# 2_0.net
KiCad netlist of a schematic drawn in Altium Designer
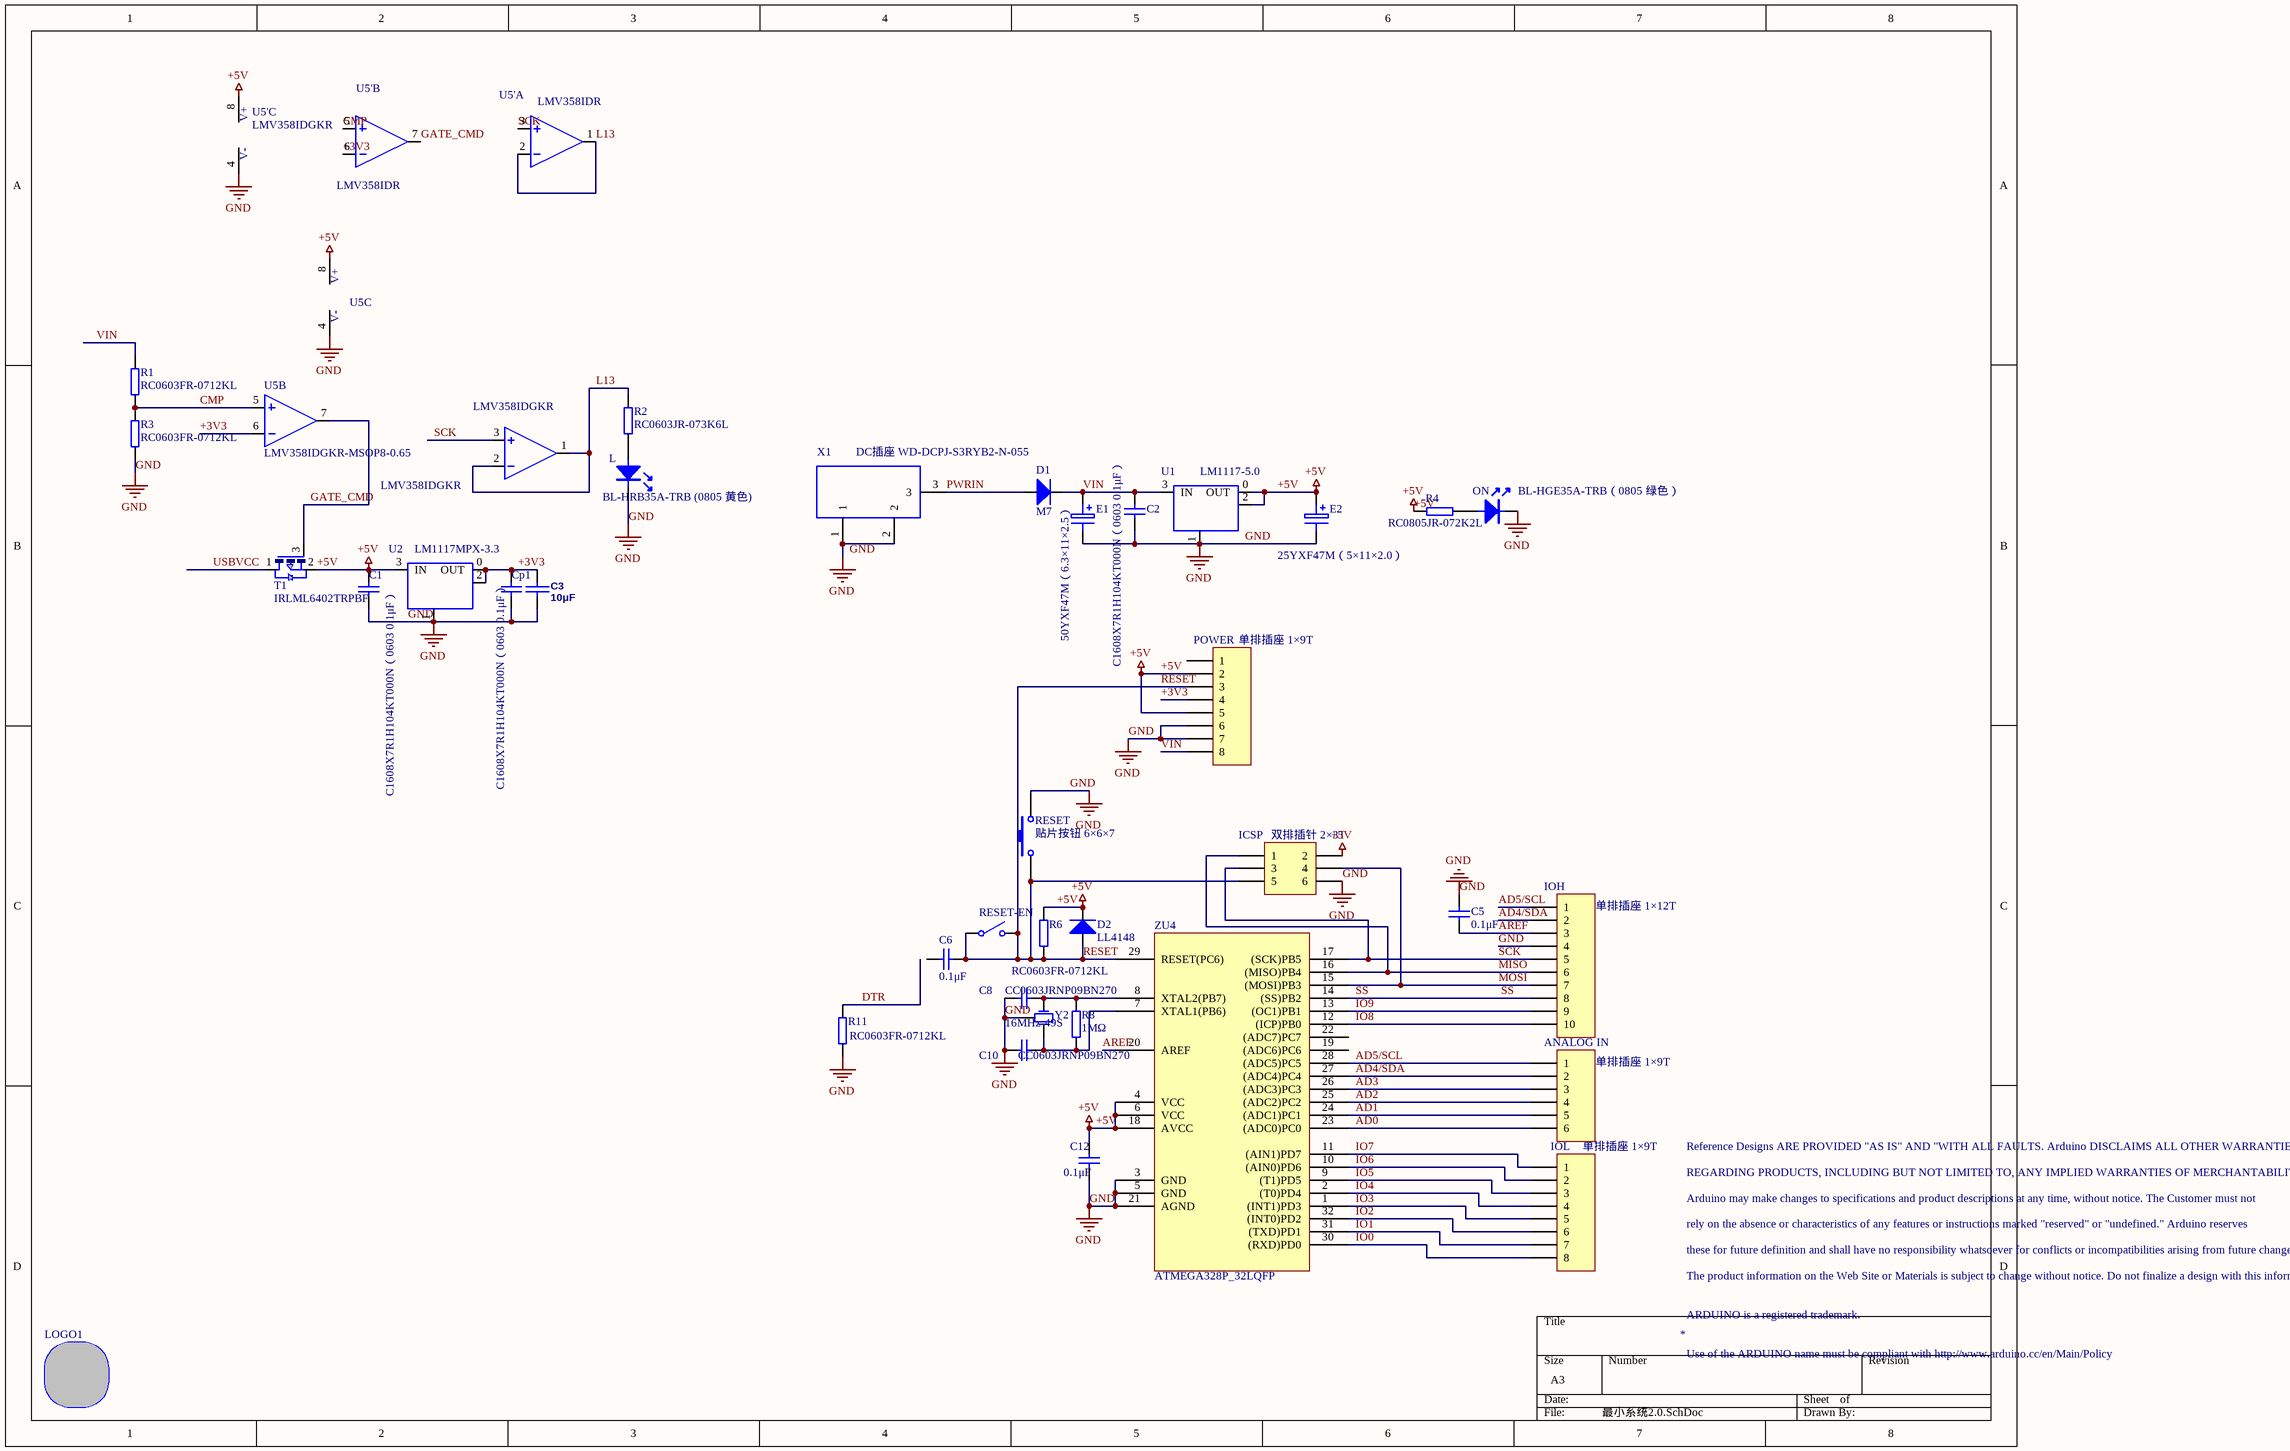
[diagram p0: 最小系统2.0.SchDoc]

(export (version "E")
  (design (tool "Eeschema 10.0.6"))
  (components
    (comp (ref "ANALOG IN")
      (value "单排插座 1×9T")
      (footprint "HDR1X6Z")
      (description "Header, 6-Pin")
      (fields (field (name "PUBLISHER") "Altium Limited"))
      (libsource (lib "Miscellaneous Connectors") (part "Header 6"))
    )
    (comp (ref "C1")
      (value "C1608X7R1H104KT000N（0603 0.1μF）")
      (footprint "0603C")
      (description "Capacitor")
      (fields (field (name "PUBLISHER") "Altium Limited"))
      (libsource (lib "*") (part "Cap"))
    )
    (comp (ref "C2")
      (value "C1608X7R1H104KT000N（0603 0.1μF）")
      (footprint "0603C")
      (description "Capacitor")
      (fields (field (name "PUBLISHER") "Altium Limited"))
      (libsource (lib "Miscellaneous Devices") (part "Cap"))
    )
    (comp (ref "C3")
      (value "10μF")
      (footprint "1206C")
      (description "Capacitor")
      (libsource (lib "*") (part "CAP"))
    )
    (comp (ref "C5")
      (value "0.1μF")
      (footprint "0603C")
      (description "Capacitor")
      (fields (field (name "PUBLISHER") "Altium Limited"))
      (libsource (lib "Miscellaneous Devices") (part "Cap"))
    )
    (comp (ref "C6")
      (value "0.1μF")
      (footprint "0603C")
      (description "Capacitor")
      (fields (field (name "PUBLISHER") "Altium Limited"))
      (libsource (lib "Miscellaneous Devices") (part "Cap"))
    )
    (comp (ref "C8")
      (value "CC0603JRNP09BN270")
      (footprint "0603C")
      (description "Capacitor")
      (fields (field (name "PUBLISHER") "Altium Limited"))
      (libsource (lib "Miscellaneous Devices") (part "Cap"))
    )
    (comp (ref "C10")
      (value "CC0603JRNP09BN270")
      (footprint "0603C")
      (description "Capacitor")
      (fields (field (name "PUBLISHER") "Altium Limited"))
      (libsource (lib "Miscellaneous Devices") (part "Cap"))
    )
    (comp (ref "C12")
      (value "0.1μF")
      (footprint "0603C")
      (description "Capacitor")
      (fields (field (name "PUBLISHER") "Altium Limited"))
      (libsource (lib "Miscellaneous Devices") (part "Cap"))
    )
    (comp (ref "Cp1")
      (value "C1608X7R1H104KT000N（0603 0.1μF）")
      (footprint "0603C")
      (description "Capacitor")
      (fields (field (name "PUBLISHER") "Altium Limited"))
      (libsource (lib "*") (part "Cap"))
    )
    (comp (ref "D1")
      (value "M7")
      (footprint "M7")
      (description "D")
      (libsource (lib "Miscellaneous Devices") (part "M7"))
    )
    (comp (ref "D2")
      (value "LL4148")
      (footprint "D1206")
      (description "D")
      (libsource (lib "Miscellaneous Devices") (part "M7"))
    )
    (comp (ref "E1")
      (value "50YXF47M（6.3×11×2.5）")
      (footprint "RB 6.3×11×2.5")
      (libsource (lib "Miscellaneous Devices") (part "E"))
    )
    (comp (ref "E2")
      (value "25YXF47M（5×11×2.0）")
      (footprint "RB 6.3×11×2.5")
      (libsource (lib "Miscellaneous Devices") (part "E"))
    )
    (comp (ref "ICSP")
      (value "双排插针 2×3T")
      (footprint "HDR2X3")
      (description "Header, 3-Pin, Dual row")
      (fields (field (name "PUBLISHER") "Altium Limited"))
      (libsource (lib "Miscellaneous Connectors") (part "Header 3X2"))
    )
    (comp (ref "IOH")
      (value "单排插座 1×12T")
      (footprint "HDR1X10Z")
      (description "Header, 10-Pin")
      (fields (field (name "PUBLISHER") "Altium Limited"))
      (libsource (lib "Miscellaneous Connectors") (part "Header 10"))
    )
    (comp (ref "IOL")
      (value "单排插座 1×9T")
      (footprint "HDR1X8Z")
      (description "Header, 8-Pin")
      (fields (field (name "PUBLISHER") "Altium Limited"))
      (libsource (lib "Miscellaneous Connectors") (part "Header 8"))
    )
    (comp (ref "L")
      (value "BL-HRB35A-TRB (0805 黄色)")
      (footprint "LED0805-Y")
      (libsource (lib "Miscellaneous Devices") (part "LED"))
    )
    (comp (ref "LOGO1")
      (value "LOGO")
      (footprint "USB_LOGO")
      (libsource (lib "Miscellaneous Connectors") (part "LOGO"))
    )
    (comp (ref "ON")
      (value "BL-HGE35A-TRB（0805 绿色）")
      (footprint "LED0805-R")
      (libsource (lib "Miscellaneous Devices") (part "LED"))
    )
    (comp (ref "POWER")
      (value "单排插座 1×9T")
      (footprint "HDR1X8Z")
      (description "Header, 8-Pin")
      (fields (field (name "PUBLISHER") "Altium Limited"))
      (libsource (lib "Miscellaneous Connectors") (part "Header 8"))
    )
    (comp (ref "R1")
      (value "RC0603FR-0712KL")
      (footprint "0603R")
      (description "Resistor")
      (libsource (lib "Miscellaneous Devices") (part "R"))
    )
    (comp (ref "R2")
      (value "RC0603JR-073K6L")
      (footprint "0603R")
      (description "Resistor")
      (libsource (lib "Miscellaneous Devices") (part "R"))
    )
    (comp (ref "R3")
      (value "RC0603FR-0712KL")
      (footprint "0603R")
      (description "Resistor")
      (libsource (lib "Miscellaneous Devices") (part "R"))
    )
    (comp (ref "R4")
      (value "RC0805JR-072K2L")
      (footprint "0805/R")
      (description "Resistor")
      (libsource (lib "Miscellaneous Devices") (part "R"))
    )
    (comp (ref "R6")
      (value "RC0603FR-0712KL")
      (footprint "0603R")
      (description "Resistor")
      (libsource (lib "Miscellaneous Devices") (part "R"))
    )
    (comp (ref "R8")
      (value "1MΩ")
      (footprint "0603R")
      (description "Resistor")
      (libsource (lib "Miscellaneous Devices") (part "R"))
    )
    (comp (ref "R11")
      (value "RC0603FR-0712KL")
      (footprint "0603R")
      (description "Resistor")
      (libsource (lib "Miscellaneous Devices") (part "R"))
    )
    (comp (ref "RESET")
      (value "贴片按钮 6×6×7")
      (footprint "按钮/SO")
      (description "Switch")
      (fields (field (name "PUBLISHER") "Altium Limited"))
      (libsource (lib "Miscellaneous Devices") (part "SW-PB"))
    )
    (comp (ref "RESET-EN")
      (value "~")
      (footprint "0101")
      (description "Single-Pole, Single-Throw Switch")
      (fields (field (name "PUBLISHER") "Altium Limited"))
      (libsource (lib "Miscellaneous Devices") (part "SW-SPST"))
    )
    (comp (ref "T1")
      (value "IRLML6402TRPBF")
      (footprint "MOSFET")
      (libsource (lib "Miscellaneous Devices") (part "PMOSSOT23"))
    )
    (comp (ref "U$1") (value "*") (footprint "MARK") (libsource (lib "SmartPrj") (part "DISCLAIMER")))
    (comp (ref "U1")
      (value "LM1117-5.0")
      (footprint "SOT223")
      (libsource (lib "Miscellaneous Devices") (part "LM1117"))
    )
    (comp (ref "U2")
      (value "LM1117MPX-3.3")
      (footprint "SOT223")
      (libsource (lib "Miscellaneous Devices") (part "LM1117"))
    )
    (comp (ref "U5")
      (value "LMV358IDGKR")
      (footprint "MSOP8-0.65")
      (libsource (lib "Miscellaneous Devices") (part "LMV358MMX"))
    )
    (comp (ref "U5'")
      (value "LMV358IDR")
      (footprint "so-8")
      (libsource (lib "Miscellaneous Devices") (part "LMV358MMX"))
    )
    (comp (ref "X1")
      (value "DC插座 WD-DCPJ-S3RYB2-N-055")
      (footprint "DC_IN")
      (description "POWERSUPPLY_DC21MMX")
      (libsource (lib "Miscellaneous Connectors") (part "DC_IN"))
    )
    (comp (ref "Y2")
      (value "16MHz-49S")
      (footprint "XTAL-49S")
      (description "3pXTAL")
      (libsource (lib "Miscellaneous Devices") (part "XTAL1"))
    )
    (comp (ref "ZU4")
      (value "ATMEGA328P_32LQFP")
      (footprint "LQFP32")
      (description "Arduino ATMEGA328P")
      (libsource (lib "Miscellaneous Devices") (part "ATMEGA328P_32LQFP"))
    )
  )
  (nets
    (net (code "1") (name "+5V") (class "Default")
      (node (ref "C1") (pin "1") (pinfunction "1_1") (pintype "passive"))
      (node (ref "C12") (pin "2") (pinfunction "2_2") (pintype "passive"))
      (node (ref "D2") (pin "K") (pinfunction "K_K") (pintype "passive"))
      (node (ref "E2") (pin "1") (pintype "passive"))
      (node (ref "ICSP") (pin "2") (pinfunction "2_2") (pintype "passive"))
      (node (ref "POWER") (pin "2") (pinfunction "2_2") (pintype "passive"))
      (node (ref "POWER") (pin "5") (pinfunction "5_5") (pintype "passive"))
      (node (ref "R4") (pin "2") (pintype "passive"))
      (node (ref "R6") (pin "1") (pintype "passive"))
      (node (ref "T1") (pin "2") (pinfunction "S_2") (pintype "passive"))
      (node (ref "U1") (pin "0") (pinfunction "OUT_0") (pintype "passive"))
      (node (ref "U1") (pin "2") (pinfunction "OUT@1_2") (pintype "passive"))
      (node (ref "U2") (pin "3") (pinfunction "IN_3") (pintype "passive"))
      (node (ref "U5") (pin "8") (pinfunction "V+_8") (pintype "passive"))
      (node (ref "U5'") (pin "8") (pinfunction "V+_8") (pintype "passive"))
      (node (ref "ZU4") (pin "18") (pinfunction "AVCC_18") (pintype "passive"))
      (node (ref "ZU4") (pin "4") (pinfunction "VCC_4") (pintype "passive"))
      (node (ref "ZU4") (pin "6") (pinfunction "VCC_6") (pintype "passive"))
    )
    (net (code "2") (name "/+3V3") (class "Default")
      (node (ref "C3") (pin "2") (pinfunction "2_2") (pintype "passive"))
      (node (ref "Cp1") (pin "1") (pinfunction "1_1") (pintype "passive"))
      (node (ref "POWER") (pin "4") (pinfunction "4_4") (pintype "passive"))
      (node (ref "U2") (pin "0") (pinfunction "OUT_0") (pintype "passive"))
      (node (ref "U2") (pin "2") (pinfunction "OUT@1_2") (pintype "passive"))
      (node (ref "U5") (pin "6") (pinfunction "-IN_6") (pintype "passive"))
      (node (ref "U5'") (pin "6") (pinfunction "-IN_6") (pintype "passive"))
    )
    (net (code "3") (name "/AD0") (class "Default")
      (node (ref "ANALOG IN") (pin "6") (pinfunction "6_6") (pintype "passive"))
      (node (ref "ZU4") (pin "23") (pinfunction "(ADC0)PC0_23") (pintype "passive"))
    )
    (net (code "4") (name "/AD1") (class "Default")
      (node (ref "ANALOG IN") (pin "5") (pinfunction "5_5") (pintype "passive"))
      (node (ref "ZU4") (pin "24") (pinfunction "(ADC1)PC1_24") (pintype "passive"))
    )
    (net (code "5") (name "/AD2") (class "Default")
      (node (ref "ANALOG IN") (pin "4") (pinfunction "4_4") (pintype "passive"))
      (node (ref "ZU4") (pin "25") (pinfunction "(ADC2)PC2_25") (pintype "passive"))
    )
    (net (code "6") (name "/AD3") (class "Default")
      (node (ref "ANALOG IN") (pin "3") (pinfunction "3_3") (pintype "passive"))
      (node (ref "ZU4") (pin "26") (pinfunction "(ADC3)PC3_26") (pintype "passive"))
    )
    (net (code "7") (name "/AD4{slash}SDA") (class "Default")
      (node (ref "ANALOG IN") (pin "2") (pinfunction "2_2") (pintype "passive"))
      (node (ref "IOH") (pin "2") (pinfunction "2_2") (pintype "passive"))
      (node (ref "ZU4") (pin "27") (pinfunction "(ADC4)PC4_27") (pintype "passive"))
    )
    (net (code "8") (name "/AD5{slash}SCL") (class "Default")
      (node (ref "ANALOG IN") (pin "1") (pinfunction "1_1") (pintype "passive"))
      (node (ref "IOH") (pin "1") (pinfunction "1_1") (pintype "passive"))
      (node (ref "ZU4") (pin "28") (pinfunction "(ADC5)PC5_28") (pintype "passive"))
    )
    (net (code "9") (name "/AREF") (class "Default")
      (node (ref "C5") (pin "1") (pinfunction "1_1") (pintype "passive"))
      (node (ref "IOH") (pin "3") (pinfunction "3_3") (pintype "passive"))
      (node (ref "ZU4") (pin "20") (pinfunction "AREF_20") (pintype "passive"))
    )
    (net (code "10") (name "/CMP") (class "Default")
      (node (ref "R1") (pin "2") (pintype "passive"))
      (node (ref "R3") (pin "1") (pintype "passive"))
      (node (ref "U5") (pin "5") (pinfunction "+IN_5") (pintype "passive"))
      (node (ref "U5'") (pin "5") (pinfunction "+IN_5") (pintype "passive"))
    )
    (net (code "11") (name "/DTR") (class "Default") (node (ref "R11") (pin "1") (pintype "passive")))
    (net (code "12") (name "/GATE_CMD") (class "Default")
      (node (ref "T1") (pin "3") (pinfunction "G_3") (pintype "passive"))
      (node (ref "U5") (pin "7") (pinfunction "OUT_7") (pintype "passive"))
      (node (ref "U5'") (pin "7") (pinfunction "OUT_7") (pintype "passive"))
    )
    (net (code "13") (name "/IO0") (class "Default")
      (node (ref "IOL") (pin "8") (pinfunction "8_8") (pintype "passive"))
      (node (ref "ZU4") (pin "30") (pinfunction "(RXD)PD0_30") (pintype "passive"))
    )
    (net (code "14") (name "/IO1") (class "Default")
      (node (ref "IOL") (pin "7") (pinfunction "7_7") (pintype "passive"))
      (node (ref "ZU4") (pin "31") (pinfunction "(TXD)PD1_31") (pintype "passive"))
    )
    (net (code "15") (name "/IO2") (class "Default")
      (node (ref "IOL") (pin "6") (pinfunction "6_6") (pintype "passive"))
      (node (ref "ZU4") (pin "32") (pinfunction "(INT0)PD2_32") (pintype "passive"))
    )
    (net (code "16") (name "/IO3") (class "Default")
      (node (ref "IOL") (pin "5") (pinfunction "5_5") (pintype "passive"))
      (node (ref "ZU4") (pin "1") (pinfunction "(INT1)PD3_1") (pintype "passive"))
    )
    (net (code "17") (name "/IO4") (class "Default")
      (node (ref "IOL") (pin "4") (pinfunction "4_4") (pintype "passive"))
      (node (ref "ZU4") (pin "2") (pinfunction "(T0)PD4_2") (pintype "passive"))
    )
    (net (code "18") (name "/IO5") (class "Default")
      (node (ref "IOL") (pin "3") (pinfunction "3_3") (pintype "passive"))
      (node (ref "ZU4") (pin "9") (pinfunction "(T1)PD5_9") (pintype "passive"))
    )
    (net (code "19") (name "/IO6") (class "Default")
      (node (ref "IOL") (pin "2") (pinfunction "2_2") (pintype "passive"))
      (node (ref "ZU4") (pin "10") (pinfunction "(AIN0)PD6_10") (pintype "passive"))
    )
    (net (code "20") (name "/IO7") (class "Default")
      (node (ref "IOL") (pin "1") (pinfunction "1_1") (pintype "passive"))
      (node (ref "ZU4") (pin "11") (pinfunction "(AIN1)PD7_11") (pintype "passive"))
    )
    (net (code "21") (name "/IO8") (class "Default")
      (node (ref "IOH") (pin "10") (pinfunction "10_10") (pintype "passive"))
      (node (ref "ZU4") (pin "12") (pinfunction "(ICP)PB0_12") (pintype "passive"))
    )
    (net (code "22") (name "/IO9") (class "Default")
      (node (ref "IOH") (pin "9") (pinfunction "9_9") (pintype "passive"))
      (node (ref "ZU4") (pin "13") (pinfunction "(OC1)PB1_13") (pintype "passive"))
    )
    (net (code "23") (name "/L13") (class "Default")
      (node (ref "R2") (pin "1") (pintype "passive"))
      (node (ref "U5") (pin "1") (pinfunction "OUT_1") (pintype "passive"))
      (node (ref "U5") (pin "2") (pinfunction "-IN_2") (pintype "passive"))
      (node (ref "U5'") (pin "1") (pinfunction "OUT_1") (pintype "passive"))
      (node (ref "U5'") (pin "2") (pinfunction "-IN_2") (pintype "passive"))
    )
    (net (code "24") (name "/MISO") (class "Default")
      (node (ref "ICSP") (pin "1") (pinfunction "1_1") (pintype "passive"))
      (node (ref "IOH") (pin "6") (pinfunction "6_6") (pintype "passive"))
      (node (ref "ZU4") (pin "16") (pinfunction "(MISO)PB4_16") (pintype "passive"))
    )
    (net (code "25") (name "/MOSI") (class "Default")
      (node (ref "ICSP") (pin "4") (pinfunction "4_4") (pintype "passive"))
      (node (ref "IOH") (pin "7") (pinfunction "7_7") (pintype "passive"))
      (node (ref "ZU4") (pin "15") (pinfunction "(MOSI)PB3_15") (pintype "passive"))
    )
    (net (code "26") (name "/PWRIN") (class "Default")
      (node (ref "D1") (pin "A") (pinfunction "A_A") (pintype "passive"))
      (node (ref "X1") (pin "3") (pinfunction "3_3") (pintype "passive"))
    )
    (net (code "27") (name "/RESET") (class "Default")
      (node (ref "C6") (pin "2") (pinfunction "2_2") (pintype "passive"))
      (node (ref "D2") (pin "A") (pinfunction "A_A") (pintype "passive"))
      (node (ref "ICSP") (pin "5") (pinfunction "5_5") (pintype "passive"))
      (node (ref "POWER") (pin "3") (pinfunction "3_3") (pintype "passive"))
      (node (ref "R6") (pin "2") (pintype "passive"))
      (node (ref "RESET") (pin "1") (pinfunction "1_1") (pintype "passive"))
      (node (ref "RESET-EN") (pin "1") (pinfunction "COMMON_1") (pintype "passive"))
      (node (ref "RESET-EN") (pin "2") (pinfunction "NO_2") (pintype "passive"))
      (node (ref "ZU4") (pin "29") (pinfunction "RESET(PC6)_29") (pintype "passive"))
    )
    (net (code "28") (name "/SCK") (class "Default")
      (node (ref "ICSP") (pin "3") (pinfunction "3_3") (pintype "passive"))
      (node (ref "IOH") (pin "5") (pinfunction "5_5") (pintype "passive"))
      (node (ref "U5") (pin "3") (pinfunction "+IN_3") (pintype "passive"))
      (node (ref "U5'") (pin "3") (pinfunction "+IN_3") (pintype "passive"))
      (node (ref "ZU4") (pin "17") (pinfunction "(SCK)PB5_17") (pintype "passive"))
    )
    (net (code "29") (name "/SS") (class "Default")
      (node (ref "IOH") (pin "8") (pinfunction "8_8") (pintype "passive"))
      (node (ref "ZU4") (pin "14") (pinfunction "(SS)PB2_14") (pintype "passive"))
    )
    (net (code "30") (name "/USBVCC") (class "Default")
      (node (ref "T1") (pin "1") (pinfunction "D_1") (pintype "passive"))
    )
    (net (code "31") (name "/VIN") (class "Default")
      (node (ref "C2") (pin "2") (pinfunction "2_2") (pintype "passive"))
      (node (ref "D1") (pin "K") (pinfunction "K_K") (pintype "passive"))
      (node (ref "E1") (pin "1") (pintype "passive"))
      (node (ref "POWER") (pin "8") (pinfunction "8_8") (pintype "passive"))
      (node (ref "R1") (pin "1") (pintype "passive"))
      (node (ref "U1") (pin "3") (pinfunction "IN_3") (pintype "passive"))
    )
    (net (code "32") (name "GND") (class "Default")
      (node (ref "C1") (pin "2") (pinfunction "2_2") (pintype "passive"))
      (node (ref "C10") (pin "1") (pinfunction "1_1") (pintype "passive"))
      (node (ref "C12") (pin "1") (pinfunction "1_1") (pintype "passive"))
      (node (ref "C2") (pin "1") (pinfunction "1_1") (pintype "passive"))
      (node (ref "C3") (pin "1") (pinfunction "1_1") (pintype "passive"))
      (node (ref "C5") (pin "2") (pinfunction "2_2") (pintype "passive"))
      (node (ref "C8") (pin "1") (pinfunction "1_1") (pintype "passive"))
      (node (ref "Cp1") (pin "2") (pinfunction "2_2") (pintype "passive"))
      (node (ref "E1") (pin "2") (pintype "passive"))
      (node (ref "E2") (pin "2") (pintype "passive"))
      (node (ref "ICSP") (pin "6") (pinfunction "6_6") (pintype "passive"))
      (node (ref "IOH") (pin "4") (pinfunction "4_4") (pintype "passive"))
      (node (ref "L") (pin "K") (pintype "passive"))
      (node (ref "ON") (pin "K") (pintype "passive"))
      (node (ref "POWER") (pin "6") (pinfunction "6_6") (pintype "passive"))
      (node (ref "POWER") (pin "7") (pinfunction "7_7") (pintype "passive"))
      (node (ref "R11") (pin "2") (pintype "passive"))
      (node (ref "R3") (pin "2") (pintype "passive"))
      (node (ref "RESET") (pin "2") (pinfunction "2_2") (pintype "passive"))
      (node (ref "U1") (pin "1") (pinfunction "GND/ADJ_1") (pintype "passive"))
      (node (ref "U2") (pin "1") (pinfunction "GND/ADJ_1") (pintype "passive"))
      (node (ref "U5") (pin "4") (pinfunction "V-_4") (pintype "passive"))
      (node (ref "U5'") (pin "4") (pinfunction "V-_4") (pintype "passive"))
      (node (ref "X1") (pin "1") (pinfunction "1_1") (pintype "passive"))
      (node (ref "X1") (pin "2") (pinfunction "2_2") (pintype "passive"))
      (node (ref "Y2") (pin "3") (pinfunction "3_3") (pintype "passive"))
      (node (ref "ZU4") (pin "21") (pinfunction "AGND_21") (pintype "passive"))
      (node (ref "ZU4") (pin "3") (pinfunction "GND_3") (pintype "passive"))
      (node (ref "ZU4") (pin "5") (pinfunction "GND_5") (pintype "passive"))
    )
    (net (code "33") (name "Net-(L-PadA)") (class "Default")
      (node (ref "L") (pin "A") (pintype "passive"))
      (node (ref "R2") (pin "2") (pintype "passive"))
    )
    (net (code "34") (name "Net-(ON-PadA)") (class "Default")
      (node (ref "ON") (pin "A") (pintype "passive"))
      (node (ref "R4") (pin "1") (pintype "passive"))
    )
    (net (code "35") (name "Net-(Y2-OSC1)") (class "Default")
      (node (ref "C8") (pin "2") (pinfunction "2_2") (pintype "passive"))
      (node (ref "R8") (pin "1") (pintype "passive"))
      (node (ref "Y2") (pin "1") (pinfunction "OSC1_1") (pintype "passive"))
      (node (ref "ZU4") (pin "8") (pinfunction "XTAL2(PB7)_8") (pintype "passive"))
    )
    (net (code "36") (name "Net-(Y2-OSC2)") (class "Default")
      (node (ref "C10") (pin "2") (pinfunction "2_2") (pintype "passive"))
      (node (ref "R8") (pin "2") (pintype "passive"))
      (node (ref "Y2") (pin "2") (pinfunction "OSC2_2") (pintype "passive"))
      (node (ref "ZU4") (pin "7") (pinfunction "XTAL1(PB6)_7") (pintype "passive"))
    )
    (net (code "37") (name "unconnected-(C6-Pad1)") (class "Default")
      (node (ref "C6") (pin "1") (pinfunction "1_1") (pintype "passive"))
    )
    (net (code "38") (name "unconnected-(POWER-Pad1)") (class "Default")
      (node (ref "POWER") (pin "1") (pinfunction "1_1") (pintype "passive"))
    )
    (net (code "39") (name "unconnected-(ZU4-(ADC6)PC6-Pad19)") (class "Default")
      (node (ref "ZU4") (pin "19") (pinfunction "(ADC6)PC6_19") (pintype "passive"))
    )
    (net (code "40") (name "unconnected-(ZU4-(ADC7)PC7-Pad22)") (class "Default")
      (node (ref "ZU4") (pin "22") (pinfunction "(ADC7)PC7_22") (pintype "passive"))
    )
  )
)
